# MCU.net
KiCad netlist of a schematic drawn in Altium Designer
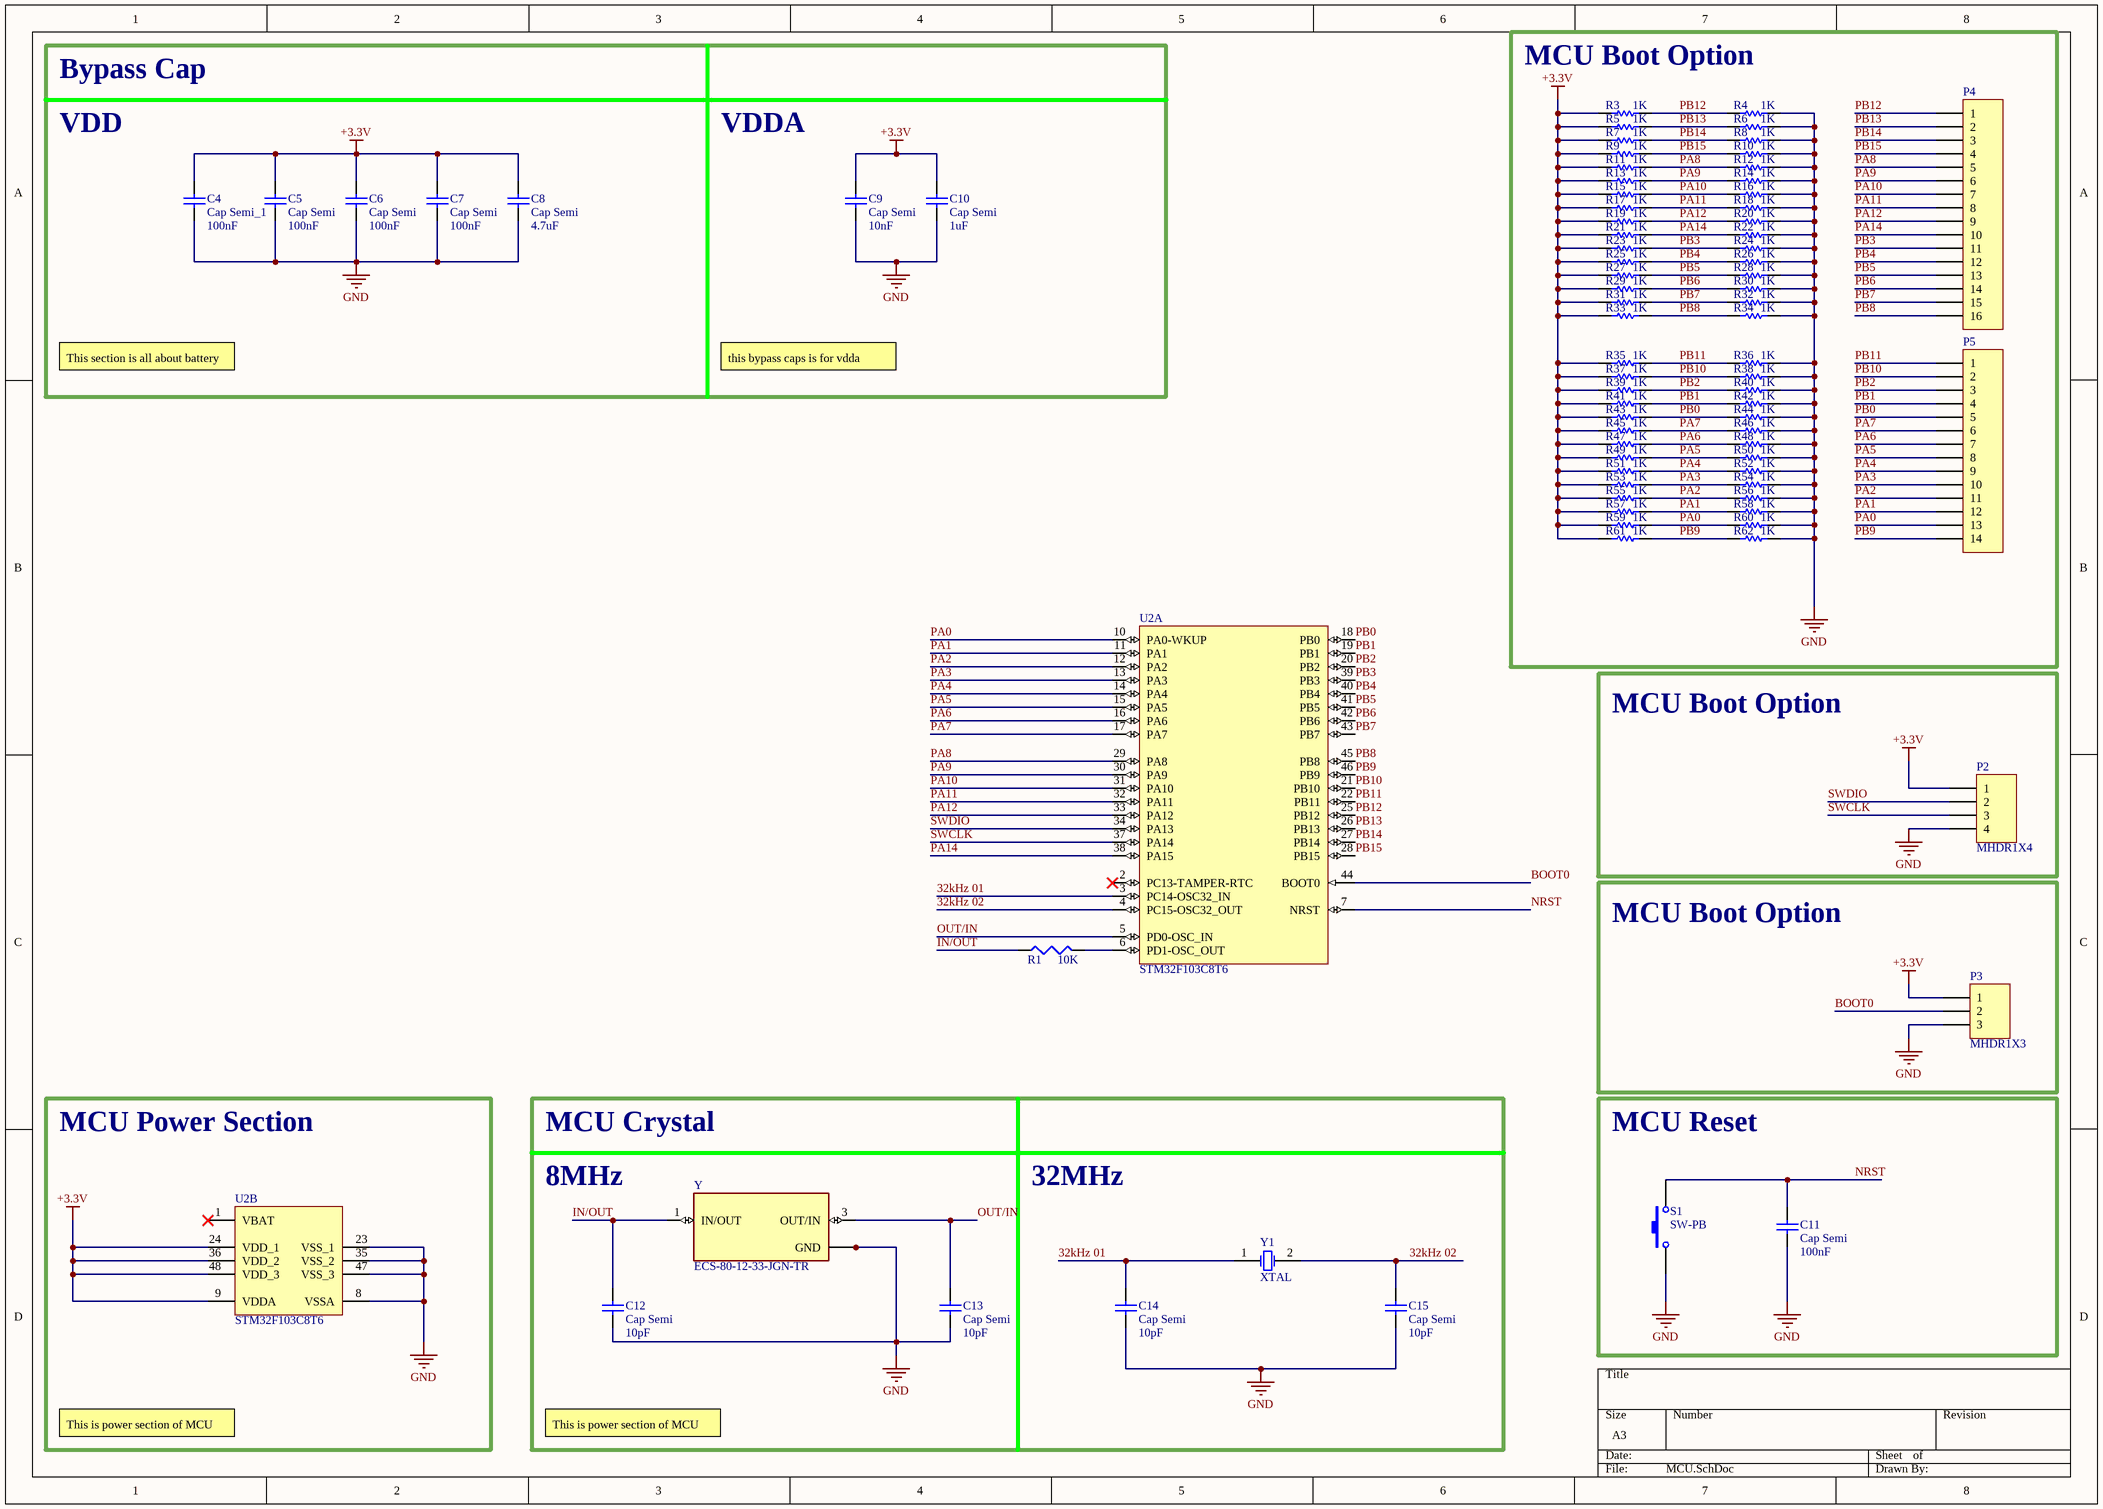
[diagram p0: MCU.SchDoc]

(export (version "E")
  (design (tool "Eeschema 10.0.6"))
  (components
    (comp (ref "C4")
      (value "Cap Semi_1")
      (footprint "1608[0603]")
      (description "Capacitor (Semiconductor SIM Model)")
      (fields (field (name "ALTIUM_VALUE") "100nF") (field (name "PUBLISHER") "Altium Limited"))
      (libsource (lib "Udemy Course") (part "Cap Semi_1"))
    )
    (comp (ref "C5")
      (value "Cap Semi")
      (footprint "1608[0603]")
      (description "Capacitor (Semiconductor SIM Model)")
      (fields (field (name "ALTIUM_VALUE") "100nF") (field (name "PUBLISHER") "Altium Limited"))
      (libsource (lib "Miscellaneous Devices") (part "Cap Semi"))
    )
    (comp (ref "C6")
      (value "Cap Semi")
      (footprint "1608[0603]")
      (description "Capacitor (Semiconductor SIM Model)")
      (fields (field (name "ALTIUM_VALUE") "100nF") (field (name "PUBLISHER") "Altium Limited"))
      (libsource (lib "Miscellaneous Devices") (part "Cap Semi"))
    )
    (comp (ref "C7")
      (value "Cap Semi")
      (footprint "1608[0603]")
      (description "Capacitor (Semiconductor SIM Model)")
      (fields (field (name "ALTIUM_VALUE") "100nF") (field (name "PUBLISHER") "Altium Limited"))
      (libsource (lib "Miscellaneous Devices") (part "Cap Semi"))
    )
    (comp (ref "C8")
      (value "Cap Semi")
      (footprint "1608[0603]")
      (description "Capacitor (Semiconductor SIM Model)")
      (fields (field (name "ALTIUM_VALUE") "4.7uF") (field (name "PUBLISHER") "Altium Limited"))
      (libsource (lib "Miscellaneous Devices") (part "Cap Semi"))
    )
    (comp (ref "C9")
      (value "Cap Semi")
      (footprint "1608[0603]")
      (description "Capacitor (Semiconductor SIM Model)")
      (fields (field (name "ALTIUM_VALUE") "10nF") (field (name "PUBLISHER") "Altium Limited"))
      (libsource (lib "Miscellaneous Devices") (part "Cap Semi"))
    )
    (comp (ref "C10")
      (value "Cap Semi")
      (footprint "1608[0603]")
      (description "Capacitor (Semiconductor SIM Model)")
      (fields (field (name "ALTIUM_VALUE") "1uF") (field (name "PUBLISHER") "Altium Limited"))
      (libsource (lib "Miscellaneous Devices") (part "Cap Semi"))
    )
    (comp (ref "C11")
      (value "Cap Semi")
      (footprint "1608[0603]")
      (description "Capacitor (Semiconductor SIM Model)")
      (fields (field (name "ALTIUM_VALUE") "100nF") (field (name "PUBLISHER") "Altium Limited"))
      (libsource (lib "Miscellaneous Devices") (part "Cap Semi"))
    )
    (comp (ref "C12")
      (value "Cap Semi")
      (footprint "0402")
      (description "Capacitor (Semiconductor SIM Model)")
      (fields (field (name "ALTIUM_VALUE") "10pF") (field (name "PUBLISHER") "Altium Limited"))
      (libsource (lib "Miscellaneous Devices") (part "Cap Semi"))
    )
    (comp (ref "C13")
      (value "Cap Semi")
      (footprint "0402")
      (description "Capacitor (Semiconductor SIM Model)")
      (fields (field (name "ALTIUM_VALUE") "10pF") (field (name "PUBLISHER") "Altium Limited"))
      (libsource (lib "Miscellaneous Devices") (part "Cap Semi"))
    )
    (comp (ref "C14")
      (value "Cap Semi")
      (footprint "0402")
      (description "Capacitor (Semiconductor SIM Model)")
      (fields (field (name "ALTIUM_VALUE") "10pF") (field (name "PUBLISHER") "Altium Limited"))
      (libsource (lib "Miscellaneous Devices") (part "Cap Semi"))
    )
    (comp (ref "C15")
      (value "Cap Semi")
      (footprint "0402")
      (description "Capacitor (Semiconductor SIM Model)")
      (fields (field (name "ALTIUM_VALUE") "10pF") (field (name "PUBLISHER") "Altium Limited"))
      (libsource (lib "Miscellaneous Devices") (part "Cap Semi"))
    )
    (comp (ref "P2")
      (value "MHDR1X4")
      (footprint "MHDR1X4body")
      (description "Header, 4-Pin")
      (fields (field (name "PUBLISHER") "Altium Limited"))
      (libsource (lib "Miscellaneous Connectors") (part "MHDR1X4"))
    )
    (comp (ref "P3")
      (value "MHDR1X3")
      (footprint "MHDR1X3body")
      (description "Header, 3-Pin")
      (fields (field (name "PUBLISHER") "Altium Limited"))
      (libsource (lib "Miscellaneous Connectors") (part "MHDR1X3"))
    )
    (comp (ref "P4")
      (value "Header 16")
      (footprint "MY_FE16")
      (description "Header, 16-Pin")
      (fields (field (name "ASID PART NUMBER") "Header 16-AS"))
      (libsource (lib "Udemy Library") (part "Header 16"))
    )
    (comp (ref "P5")
      (value "Header 14")
      (footprint "MY_FE14")
      (description "Header, 14-Pin")
      (fields (field (name "ASID PART NUMBER") "Header 14-AS"))
      (libsource (lib "Udemy Library") (part "Header 14"))
    )
    (comp (ref "R1")
      (value "10K")
      (footprint "J1-0603")
      (description "Resistor")
      (fields (field (name "Comment") "Res3") (field (name "PUBLISHER") "Altium Limited"))
      (libsource (lib "Miscellaneous Devices") (part "Res3"))
    )
    (comp (ref "R3")
      (value "1K")
      (footprint "MY_0603")
      (description "Standard resistor")
      (fields (field (name "ASID PART NUMBER") "Res-AS"))
      (libsource (lib "Udemy Library") (part "Res"))
    )
    (comp (ref "R4")
      (value "1K")
      (footprint "MY_0603")
      (description "Standard resistor")
      (fields (field (name "ASID PART NUMBER") "Res-AS"))
      (libsource (lib "Udemy Library") (part "Res"))
    )
    (comp (ref "R5")
      (value "1K")
      (footprint "MY_0603")
      (description "Standard resistor")
      (fields (field (name "ASID PART NUMBER") "Res-AS"))
      (libsource (lib "Udemy Library") (part "Res"))
    )
    (comp (ref "R6")
      (value "1K")
      (footprint "MY_0603")
      (description "Standard resistor")
      (fields (field (name "ASID PART NUMBER") "Res-AS"))
      (libsource (lib "Udemy Library") (part "Res"))
    )
    (comp (ref "R7")
      (value "1K")
      (footprint "MY_0603")
      (description "Standard resistor")
      (fields (field (name "ASID PART NUMBER") "Res-AS"))
      (libsource (lib "Udemy Library") (part "Res"))
    )
    (comp (ref "R8")
      (value "1K")
      (footprint "MY_0603")
      (description "Standard resistor")
      (fields (field (name "ASID PART NUMBER") "Res-AS"))
      (libsource (lib "Udemy Library") (part "Res"))
    )
    (comp (ref "R9")
      (value "1K")
      (footprint "MY_0603")
      (description "Standard resistor")
      (fields (field (name "ASID PART NUMBER") "Res-AS"))
      (libsource (lib "Udemy Library") (part "Res"))
    )
    (comp (ref "R10")
      (value "1K")
      (footprint "MY_0603")
      (description "Standard resistor")
      (fields (field (name "ASID PART NUMBER") "Res-AS"))
      (libsource (lib "Udemy Library") (part "Res"))
    )
    (comp (ref "R11")
      (value "1K")
      (footprint "MY_0603")
      (description "Standard resistor")
      (fields (field (name "ASID PART NUMBER") "Res-AS"))
      (libsource (lib "Udemy Library") (part "Res"))
    )
    (comp (ref "R12")
      (value "1K")
      (footprint "MY_0603")
      (description "Standard resistor")
      (fields (field (name "ASID PART NUMBER") "Res-AS"))
      (libsource (lib "Udemy Library") (part "Res"))
    )
    (comp (ref "R13")
      (value "1K")
      (footprint "MY_0603")
      (description "Standard resistor")
      (fields (field (name "ASID PART NUMBER") "Res-AS"))
      (libsource (lib "Udemy Library") (part "Res"))
    )
    (comp (ref "R14")
      (value "1K")
      (footprint "MY_0603")
      (description "Standard resistor")
      (fields (field (name "ASID PART NUMBER") "Res-AS"))
      (libsource (lib "Udemy Library") (part "Res"))
    )
    (comp (ref "R15")
      (value "1K")
      (footprint "MY_0603")
      (description "Standard resistor")
      (fields (field (name "ASID PART NUMBER") "Res-AS"))
      (libsource (lib "Udemy Library") (part "Res"))
    )
    (comp (ref "R16")
      (value "1K")
      (footprint "MY_0603")
      (description "Standard resistor")
      (fields (field (name "ASID PART NUMBER") "Res-AS"))
      (libsource (lib "Udemy Library") (part "Res"))
    )
    (comp (ref "R17")
      (value "1K")
      (footprint "MY_0603")
      (description "Standard resistor")
      (fields (field (name "ASID PART NUMBER") "Res-AS"))
      (libsource (lib "Udemy Library") (part "Res"))
    )
    (comp (ref "R18")
      (value "1K")
      (footprint "MY_0603")
      (description "Standard resistor")
      (fields (field (name "ASID PART NUMBER") "Res-AS"))
      (libsource (lib "Udemy Library") (part "Res"))
    )
    (comp (ref "R19")
      (value "1K")
      (footprint "MY_0603")
      (description "Standard resistor")
      (fields (field (name "ASID PART NUMBER") "Res-AS"))
      (libsource (lib "Udemy Library") (part "Res"))
    )
    (comp (ref "R20")
      (value "1K")
      (footprint "MY_0603")
      (description "Standard resistor")
      (fields (field (name "ASID PART NUMBER") "Res-AS"))
      (libsource (lib "Udemy Library") (part "Res"))
    )
    (comp (ref "R21")
      (value "1K")
      (footprint "MY_0603")
      (description "Standard resistor")
      (fields (field (name "ASID PART NUMBER") "Res-AS"))
      (libsource (lib "Udemy Library") (part "Res"))
    )
    (comp (ref "R22")
      (value "1K")
      (footprint "MY_0603")
      (description "Standard resistor")
      (fields (field (name "ASID PART NUMBER") "Res-AS"))
      (libsource (lib "Udemy Library") (part "Res"))
    )
    (comp (ref "R23")
      (value "1K")
      (footprint "MY_0603")
      (description "Standard resistor")
      (fields (field (name "ASID PART NUMBER") "Res-AS"))
      (libsource (lib "Udemy Library") (part "Res"))
    )
    (comp (ref "R24")
      (value "1K")
      (footprint "MY_0603")
      (description "Standard resistor")
      (fields (field (name "ASID PART NUMBER") "Res-AS"))
      (libsource (lib "Udemy Library") (part "Res"))
    )
    (comp (ref "R25")
      (value "1K")
      (footprint "MY_0603")
      (description "Standard resistor")
      (fields (field (name "ASID PART NUMBER") "Res-AS"))
      (libsource (lib "Udemy Library") (part "Res"))
    )
    (comp (ref "R26")
      (value "1K")
      (footprint "MY_0603")
      (description "Standard resistor")
      (fields (field (name "ASID PART NUMBER") "Res-AS"))
      (libsource (lib "Udemy Library") (part "Res"))
    )
    (comp (ref "R27")
      (value "1K")
      (footprint "MY_0603")
      (description "Standard resistor")
      (fields (field (name "ASID PART NUMBER") "Res-AS"))
      (libsource (lib "Udemy Library") (part "Res"))
    )
    (comp (ref "R28")
      (value "1K")
      (footprint "MY_0603")
      (description "Standard resistor")
      (fields (field (name "ASID PART NUMBER") "Res-AS"))
      (libsource (lib "Udemy Library") (part "Res"))
    )
    (comp (ref "R29")
      (value "1K")
      (footprint "MY_0603")
      (description "Standard resistor")
      (fields (field (name "ASID PART NUMBER") "Res-AS"))
      (libsource (lib "Udemy Library") (part "Res"))
    )
    (comp (ref "R30")
      (value "1K")
      (footprint "MY_0603")
      (description "Standard resistor")
      (fields (field (name "ASID PART NUMBER") "Res-AS"))
      (libsource (lib "Udemy Library") (part "Res"))
    )
    (comp (ref "R31")
      (value "1K")
      (footprint "MY_0603")
      (description "Standard resistor")
      (fields (field (name "ASID PART NUMBER") "Res-AS"))
      (libsource (lib "Udemy Library") (part "Res"))
    )
    (comp (ref "R32")
      (value "1K")
      (footprint "MY_0603")
      (description "Standard resistor")
      (fields (field (name "ASID PART NUMBER") "Res-AS"))
      (libsource (lib "Udemy Library") (part "Res"))
    )
    (comp (ref "R33")
      (value "1K")
      (footprint "MY_0603")
      (description "Standard resistor")
      (fields (field (name "ASID PART NUMBER") "Res-AS"))
      (libsource (lib "Udemy Library") (part "Res"))
    )
    (comp (ref "R34")
      (value "1K")
      (footprint "MY_0603")
      (description "Standard resistor")
      (fields (field (name "ASID PART NUMBER") "Res-AS"))
      (libsource (lib "Udemy Library") (part "Res"))
    )
    (comp (ref "R35")
      (value "1K")
      (footprint "MY_0603")
      (description "Standard resistor")
      (fields (field (name "ASID PART NUMBER") "Res-AS"))
      (libsource (lib "Udemy Library") (part "Res"))
    )
    (comp (ref "R36")
      (value "1K")
      (footprint "MY_0603")
      (description "Standard resistor")
      (fields (field (name "ASID PART NUMBER") "Res-AS"))
      (libsource (lib "Udemy Library") (part "Res"))
    )
    (comp (ref "R37")
      (value "1K")
      (footprint "MY_0603")
      (description "Standard resistor")
      (fields (field (name "ASID PART NUMBER") "Res-AS"))
      (libsource (lib "Udemy Library") (part "Res"))
    )
    (comp (ref "R38")
      (value "1K")
      (footprint "MY_0603")
      (description "Standard resistor")
      (fields (field (name "ASID PART NUMBER") "Res-AS"))
      (libsource (lib "Udemy Library") (part "Res"))
    )
    (comp (ref "R39")
      (value "1K")
      (footprint "MY_0603")
      (description "Standard resistor")
      (fields (field (name "ASID PART NUMBER") "Res-AS"))
      (libsource (lib "Udemy Library") (part "Res"))
    )
    (comp (ref "R40")
      (value "1K")
      (footprint "MY_0603")
      (description "Standard resistor")
      (fields (field (name "ASID PART NUMBER") "Res-AS"))
      (libsource (lib "Udemy Library") (part "Res"))
    )
    (comp (ref "R41")
      (value "1K")
      (footprint "MY_0603")
      (description "Standard resistor")
      (fields (field (name "ASID PART NUMBER") "Res-AS"))
      (libsource (lib "Udemy Library") (part "Res"))
    )
    (comp (ref "R42")
      (value "1K")
      (footprint "MY_0603")
      (description "Standard resistor")
      (fields (field (name "ASID PART NUMBER") "Res-AS"))
      (libsource (lib "Udemy Library") (part "Res"))
    )
    (comp (ref "R43")
      (value "1K")
      (footprint "MY_0603")
      (description "Standard resistor")
      (fields (field (name "ASID PART NUMBER") "Res-AS"))
      (libsource (lib "Udemy Library") (part "Res"))
    )
    (comp (ref "R44")
      (value "1K")
      (footprint "MY_0603")
      (description "Standard resistor")
      (fields (field (name "ASID PART NUMBER") "Res-AS"))
      (libsource (lib "Udemy Library") (part "Res"))
    )
    (comp (ref "R45")
      (value "1K")
      (footprint "MY_0603")
      (description "Standard resistor")
      (fields (field (name "ASID PART NUMBER") "Res-AS"))
      (libsource (lib "Udemy Library") (part "Res"))
    )
    (comp (ref "R46")
      (value "1K")
      (footprint "MY_0603")
      (description "Standard resistor")
      (fields (field (name "ASID PART NUMBER") "Res-AS"))
      (libsource (lib "Udemy Library") (part "Res"))
    )
    (comp (ref "R47")
      (value "1K")
      (footprint "MY_0603")
      (description "Standard resistor")
      (fields (field (name "ASID PART NUMBER") "Res-AS"))
      (libsource (lib "Udemy Library") (part "Res"))
    )
    (comp (ref "R48")
      (value "1K")
      (footprint "MY_0603")
      (description "Standard resistor")
      (fields (field (name "ASID PART NUMBER") "Res-AS"))
      (libsource (lib "Udemy Library") (part "Res"))
    )
    (comp (ref "R49")
      (value "1K")
      (footprint "MY_0603")
      (description "Standard resistor")
      (fields (field (name "ASID PART NUMBER") "Res-AS"))
      (libsource (lib "Udemy Library") (part "Res"))
    )
    (comp (ref "R50")
      (value "1K")
      (footprint "MY_0603")
      (description "Standard resistor")
      (fields (field (name "ASID PART NUMBER") "Res-AS"))
      (libsource (lib "Udemy Library") (part "Res"))
    )
    (comp (ref "R51")
      (value "1K")
      (footprint "MY_0603")
      (description "Standard resistor")
      (fields (field (name "ASID PART NUMBER") "Res-AS"))
      (libsource (lib "Udemy Library") (part "Res"))
    )
    (comp (ref "R52")
      (value "1K")
      (footprint "MY_0603")
      (description "Standard resistor")
      (fields (field (name "ASID PART NUMBER") "Res-AS"))
      (libsource (lib "Udemy Library") (part "Res"))
    )
    (comp (ref "R53")
      (value "1K")
      (footprint "MY_0603")
      (description "Standard resistor")
      (fields (field (name "ASID PART NUMBER") "Res-AS"))
      (libsource (lib "Udemy Library") (part "Res"))
    )
    (comp (ref "R54")
      (value "1K")
      (footprint "MY_0603")
      (description "Standard resistor")
      (fields (field (name "ASID PART NUMBER") "Res-AS"))
      (libsource (lib "Udemy Library") (part "Res"))
    )
    (comp (ref "R55")
      (value "1K")
      (footprint "MY_0603")
      (description "Standard resistor")
      (fields (field (name "ASID PART NUMBER") "Res-AS"))
      (libsource (lib "Udemy Library") (part "Res"))
    )
    (comp (ref "R56")
      (value "1K")
      (footprint "MY_0603")
      (description "Standard resistor")
      (fields (field (name "ASID PART NUMBER") "Res-AS"))
      (libsource (lib "Udemy Library") (part "Res"))
    )
    (comp (ref "R57")
      (value "1K")
      (footprint "MY_0603")
      (description "Standard resistor")
      (fields (field (name "ASID PART NUMBER") "Res-AS"))
      (libsource (lib "Udemy Library") (part "Res"))
    )
    (comp (ref "R58")
      (value "1K")
      (footprint "MY_0603")
      (description "Standard resistor")
      (fields (field (name "ASID PART NUMBER") "Res-AS"))
      (libsource (lib "Udemy Library") (part "Res"))
    )
    (comp (ref "R59")
      (value "1K")
      (footprint "MY_0603")
      (description "Standard resistor")
      (fields (field (name "ASID PART NUMBER") "Res-AS"))
      (libsource (lib "Udemy Library") (part "Res"))
    )
    (comp (ref "R60")
      (value "1K")
      (footprint "MY_0603")
      (description "Standard resistor")
      (fields (field (name "ASID PART NUMBER") "Res-AS"))
      (libsource (lib "Udemy Library") (part "Res"))
    )
    (comp (ref "R61")
      (value "1K")
      (footprint "MY_0603")
      (description "Standard resistor")
      (fields (field (name "ASID PART NUMBER") "Res-AS"))
      (libsource (lib "Udemy Library") (part "Res"))
    )
    (comp (ref "R62")
      (value "1K")
      (footprint "MY_0603")
      (description "Standard resistor")
      (fields (field (name "ASID PART NUMBER") "Res-AS"))
      (libsource (lib "Udemy Library") (part "Res"))
    )
    (comp (ref "S1")
      (value "SW-PB")
      (footprint "SPST-2_body")
      (description "Switch")
      (fields (field (name "PUBLISHER") "Altium Limited"))
      (libsource (lib "Miscellaneous Devices") (part "SW-PB"))
    )
    (comp (ref "U2")
      (value "STM32F103C8T6")
      (footprint "STM-LQFP48_N")
      (libsource (lib "PCB Udemy") (part "STM32F103C8T6"))
    )
    (comp (ref "Y")
      (value "ECS-80-12-33-JGN-TR")
      (footprint "8MHZCrystall")
      (description "8MHz Â±20ppm Crystal 12pF 400 Ohms 4-SMD, No Lead")
      (fields
        (field (name "MF") "ECS Inc.")
        (field (name "BUYPART") "https://www.snapeda.com/parts/ECS-80-12-33-JGN-TR/ECS%20Inc./view-part/4477300/?ref=eda")
      )
      (libsource (lib "ECS-80-12-33-JGN-TR") (part "ECS-80-12-33-JGN-TR"))
    )
    (comp (ref "Y1")
      (value "XTAL")
      (footprint "32768")
      (description "Crystal Oscillator")
      (fields (field (name "PUBLISHER") "Altium Limited"))
      (libsource (lib "Miscellaneous Devices") (part "XTAL"))
    )
  )
  (nets
    (net (code "1") (name "+3.3V") (class "Default")
      (node (ref "C10") (pin "2") (pinfunction "2_2") (pintype "passive"))
      (node (ref "C4") (pin "2") (pinfunction "2_2") (pintype "passive"))
      (node (ref "C5") (pin "2") (pinfunction "2_2") (pintype "passive"))
      (node (ref "C6") (pin "2") (pinfunction "2_2") (pintype "passive"))
      (node (ref "C7") (pin "2") (pinfunction "2_2") (pintype "passive"))
      (node (ref "C8") (pin "2") (pinfunction "2_2") (pintype "passive"))
      (node (ref "C9") (pin "2") (pinfunction "2_2") (pintype "passive"))
      (node (ref "P2") (pin "1") (pinfunction "1_1") (pintype "passive"))
      (node (ref "P3") (pin "1") (pinfunction "1_1") (pintype "passive"))
      (node (ref "R11") (pin "1") (pinfunction "1_1") (pintype "passive"))
      (node (ref "R13") (pin "1") (pinfunction "1_1") (pintype "passive"))
      (node (ref "R15") (pin "1") (pinfunction "1_1") (pintype "passive"))
      (node (ref "R17") (pin "1") (pinfunction "1_1") (pintype "passive"))
      (node (ref "R19") (pin "1") (pinfunction "1_1") (pintype "passive"))
      (node (ref "R21") (pin "1") (pinfunction "1_1") (pintype "passive"))
      (node (ref "R23") (pin "1") (pinfunction "1_1") (pintype "passive"))
      (node (ref "R25") (pin "1") (pinfunction "1_1") (pintype "passive"))
      (node (ref "R27") (pin "1") (pinfunction "1_1") (pintype "passive"))
      (node (ref "R29") (pin "1") (pinfunction "1_1") (pintype "passive"))
      (node (ref "R3") (pin "1") (pinfunction "1_1") (pintype "passive"))
      (node (ref "R31") (pin "1") (pinfunction "1_1") (pintype "passive"))
      (node (ref "R33") (pin "1") (pinfunction "1_1") (pintype "passive"))
      (node (ref "R35") (pin "1") (pinfunction "1_1") (pintype "passive"))
      (node (ref "R37") (pin "1") (pinfunction "1_1") (pintype "passive"))
      (node (ref "R39") (pin "1") (pinfunction "1_1") (pintype "passive"))
      (node (ref "R41") (pin "1") (pinfunction "1_1") (pintype "passive"))
      (node (ref "R43") (pin "1") (pinfunction "1_1") (pintype "passive"))
      (node (ref "R45") (pin "1") (pinfunction "1_1") (pintype "passive"))
      (node (ref "R47") (pin "1") (pinfunction "1_1") (pintype "passive"))
      (node (ref "R49") (pin "1") (pinfunction "1_1") (pintype "passive"))
      (node (ref "R5") (pin "1") (pinfunction "1_1") (pintype "passive"))
      (node (ref "R51") (pin "1") (pinfunction "1_1") (pintype "passive"))
      (node (ref "R53") (pin "1") (pinfunction "1_1") (pintype "passive"))
      (node (ref "R55") (pin "1") (pinfunction "1_1") (pintype "passive"))
      (node (ref "R57") (pin "1") (pinfunction "1_1") (pintype "passive"))
      (node (ref "R59") (pin "1") (pinfunction "1_1") (pintype "passive"))
      (node (ref "R61") (pin "1") (pinfunction "1_1") (pintype "passive"))
      (node (ref "R7") (pin "1") (pinfunction "1_1") (pintype "passive"))
      (node (ref "R9") (pin "1") (pinfunction "1_1") (pintype "passive"))
      (node (ref "U2") (pin "24") (pinfunction "VDD_1_24") (pintype "power_in"))
      (node (ref "U2") (pin "36") (pinfunction "VDD_2_36") (pintype "power_in"))
      (node (ref "U2") (pin "48") (pinfunction "VDD_3_48") (pintype "power_in"))
      (node (ref "U2") (pin "9") (pinfunction "VDDA_9") (pintype "power_in"))
    )
    (net (code "2") (name "/32kHz 01") (class "Default")
      (node (ref "C14") (pin "2") (pinfunction "2_2") (pintype "passive"))
      (node (ref "U2") (pin "3") (pinfunction "PC14-OSC32_IN_3") (pintype "bidirectional"))
      (node (ref "Y1") (pin "1") (pinfunction "OSC1_1") (pintype "passive"))
    )
    (net (code "3") (name "/32kHz 02") (class "Default")
      (node (ref "C15") (pin "2") (pinfunction "2_2") (pintype "passive"))
      (node (ref "U2") (pin "4") (pinfunction "PC15-OSC32_OUT_4") (pintype "bidirectional"))
      (node (ref "Y1") (pin "2") (pinfunction "OSC2_2") (pintype "passive"))
    )
    (net (code "4") (name "/BOOT0") (class "Default")
      (node (ref "P3") (pin "2") (pinfunction "2_2") (pintype "passive"))
      (node (ref "U2") (pin "44") (pinfunction "BOOT0_44") (pintype "input"))
    )
    (net (code "5") (name "/IN{slash}OUT") (class "Default")
      (node (ref "C12") (pin "1") (pinfunction "1_1") (pintype "passive"))
      (node (ref "R1") (pin "1") (pinfunction "1_1") (pintype "passive"))
      (node (ref "Y") (pin "1") (pinfunction "IN/OUT_1") (pintype "bidirectional"))
    )
    (net (code "6") (name "/NRST") (class "Default")
      (node (ref "C11") (pin "2") (pinfunction "2_2") (pintype "passive"))
      (node (ref "S1") (pin "2") (pinfunction "2_2") (pintype "passive"))
      (node (ref "U2") (pin "7") (pinfunction "NRST_7") (pintype "bidirectional"))
    )
    (net (code "7") (name "/OUT{slash}IN") (class "Default")
      (node (ref "C13") (pin "2") (pinfunction "2_2") (pintype "passive"))
      (node (ref "U2") (pin "5") (pinfunction "PD0-OSC_IN_5") (pintype "bidirectional"))
      (node (ref "Y") (pin "3") (pinfunction "OUT/IN_3") (pintype "bidirectional"))
    )
    (net (code "8") (name "/PA0") (class "Default")
      (node (ref "P5") (pin "13") (pinfunction "13_13") (pintype "passive"))
      (node (ref "R59") (pin "2") (pinfunction "2_2") (pintype "passive"))
      (node (ref "R60") (pin "1") (pinfunction "1_1") (pintype "passive"))
      (node (ref "U2") (pin "10") (pinfunction "PA0-WKUP_10") (pintype "bidirectional"))
    )
    (net (code "9") (name "/PA1") (class "Default")
      (node (ref "P5") (pin "12") (pinfunction "12_12") (pintype "passive"))
      (node (ref "R57") (pin "2") (pinfunction "2_2") (pintype "passive"))
      (node (ref "R58") (pin "1") (pinfunction "1_1") (pintype "passive"))
      (node (ref "U2") (pin "11") (pinfunction "PA1_11") (pintype "bidirectional"))
    )
    (net (code "10") (name "/PA2") (class "Default")
      (node (ref "P5") (pin "11") (pinfunction "11_11") (pintype "passive"))
      (node (ref "R55") (pin "2") (pinfunction "2_2") (pintype "passive"))
      (node (ref "R56") (pin "1") (pinfunction "1_1") (pintype "passive"))
      (node (ref "U2") (pin "12") (pinfunction "PA2_12") (pintype "bidirectional"))
    )
    (net (code "11") (name "/PA3") (class "Default")
      (node (ref "P5") (pin "10") (pinfunction "10_10") (pintype "passive"))
      (node (ref "R53") (pin "2") (pinfunction "2_2") (pintype "passive"))
      (node (ref "R54") (pin "1") (pinfunction "1_1") (pintype "passive"))
      (node (ref "U2") (pin "13") (pinfunction "PA3_13") (pintype "bidirectional"))
    )
    (net (code "12") (name "/PA4") (class "Default")
      (node (ref "P5") (pin "9") (pinfunction "9_9") (pintype "passive"))
      (node (ref "R51") (pin "2") (pinfunction "2_2") (pintype "passive"))
      (node (ref "R52") (pin "1") (pinfunction "1_1") (pintype "passive"))
      (node (ref "U2") (pin "14") (pinfunction "PA4_14") (pintype "bidirectional"))
    )
    (net (code "13") (name "/PA5") (class "Default")
      (node (ref "P5") (pin "8") (pinfunction "8_8") (pintype "passive"))
      (node (ref "R49") (pin "2") (pinfunction "2_2") (pintype "passive"))
      (node (ref "R50") (pin "1") (pinfunction "1_1") (pintype "passive"))
      (node (ref "U2") (pin "15") (pinfunction "PA5_15") (pintype "bidirectional"))
    )
    (net (code "14") (name "/PA6") (class "Default")
      (node (ref "P5") (pin "7") (pinfunction "7_7") (pintype "passive"))
      (node (ref "R47") (pin "2") (pinfunction "2_2") (pintype "passive"))
      (node (ref "R48") (pin "1") (pinfunction "1_1") (pintype "passive"))
      (node (ref "U2") (pin "16") (pinfunction "PA6_16") (pintype "bidirectional"))
    )
    (net (code "15") (name "/PA7") (class "Default")
      (node (ref "P5") (pin "6") (pinfunction "6_6") (pintype "passive"))
      (node (ref "R45") (pin "2") (pinfunction "2_2") (pintype "passive"))
      (node (ref "R46") (pin "1") (pinfunction "1_1") (pintype "passive"))
      (node (ref "U2") (pin "17") (pinfunction "PA7_17") (pintype "bidirectional"))
    )
    (net (code "16") (name "/PA8") (class "Default")
      (node (ref "P4") (pin "5") (pinfunction "5_5") (pintype "passive"))
      (node (ref "R11") (pin "2") (pinfunction "2_2") (pintype "passive"))
      (node (ref "R12") (pin "1") (pinfunction "1_1") (pintype "passive"))
      (node (ref "U2") (pin "29") (pinfunction "PA8_29") (pintype "bidirectional"))
    )
    (net (code "17") (name "/PA9") (class "Default")
      (node (ref "P4") (pin "6") (pinfunction "6_6") (pintype "passive"))
      (node (ref "R13") (pin "2") (pinfunction "2_2") (pintype "passive"))
      (node (ref "R14") (pin "1") (pinfunction "1_1") (pintype "passive"))
      (node (ref "U2") (pin "30") (pinfunction "PA9_30") (pintype "bidirectional"))
    )
    (net (code "18") (name "/PA10") (class "Default")
      (node (ref "P4") (pin "7") (pinfunction "7_7") (pintype "passive"))
      (node (ref "R15") (pin "2") (pinfunction "2_2") (pintype "passive"))
      (node (ref "R16") (pin "1") (pinfunction "1_1") (pintype "passive"))
      (node (ref "U2") (pin "31") (pinfunction "PA10_31") (pintype "bidirectional"))
    )
    (net (code "19") (name "/PA11") (class "Default")
      (node (ref "P4") (pin "8") (pinfunction "8_8") (pintype "passive"))
      (node (ref "R17") (pin "2") (pinfunction "2_2") (pintype "passive"))
      (node (ref "R18") (pin "1") (pinfunction "1_1") (pintype "passive"))
      (node (ref "U2") (pin "32") (pinfunction "PA11_32") (pintype "bidirectional"))
    )
    (net (code "20") (name "/PA12") (class "Default")
      (node (ref "P4") (pin "9") (pinfunction "9_9") (pintype "passive"))
      (node (ref "R19") (pin "2") (pinfunction "2_2") (pintype "passive"))
      (node (ref "R20") (pin "1") (pinfunction "1_1") (pintype "passive"))
      (node (ref "U2") (pin "33") (pinfunction "PA12_33") (pintype "bidirectional"))
    )
    (net (code "21") (name "/PA14") (class "Default")
      (node (ref "P4") (pin "10") (pinfunction "10_10") (pintype "passive"))
      (node (ref "R21") (pin "2") (pinfunction "2_2") (pintype "passive"))
      (node (ref "R22") (pin "1") (pinfunction "1_1") (pintype "passive"))
      (node (ref "U2") (pin "38") (pinfunction "PA15_38") (pintype "bidirectional"))
    )
    (net (code "22") (name "/PB0") (class "Default")
      (node (ref "P5") (pin "5") (pinfunction "5_5") (pintype "passive"))
      (node (ref "R43") (pin "2") (pinfunction "2_2") (pintype "passive"))
      (node (ref "R44") (pin "1") (pinfunction "1_1") (pintype "passive"))
      (node (ref "U2") (pin "18") (pinfunction "PB0_18") (pintype "bidirectional"))
    )
    (net (code "23") (name "/PB1") (class "Default")
      (node (ref "P5") (pin "4") (pinfunction "4_4") (pintype "passive"))
      (node (ref "R41") (pin "2") (pinfunction "2_2") (pintype "passive"))
      (node (ref "R42") (pin "1") (pinfunction "1_1") (pintype "passive"))
      (node (ref "U2") (pin "19") (pinfunction "PB1_19") (pintype "bidirectional"))
    )
    (net (code "24") (name "/PB2") (class "Default")
      (node (ref "P5") (pin "3") (pinfunction "3_3") (pintype "passive"))
      (node (ref "R39") (pin "2") (pinfunction "2_2") (pintype "passive"))
      (node (ref "R40") (pin "1") (pinfunction "1_1") (pintype "passive"))
      (node (ref "U2") (pin "20") (pinfunction "PB2_20") (pintype "bidirectional"))
    )
    (net (code "25") (name "/PB3") (class "Default")
      (node (ref "P4") (pin "11") (pinfunction "11_11") (pintype "passive"))
      (node (ref "R23") (pin "2") (pinfunction "2_2") (pintype "passive"))
      (node (ref "R24") (pin "1") (pinfunction "1_1") (pintype "passive"))
      (node (ref "U2") (pin "39") (pinfunction "PB3_39") (pintype "bidirectional"))
    )
    (net (code "26") (name "/PB4") (class "Default")
      (node (ref "P4") (pin "12") (pinfunction "12_12") (pintype "passive"))
      (node (ref "R25") (pin "2") (pinfunction "2_2") (pintype "passive"))
      (node (ref "R26") (pin "1") (pinfunction "1_1") (pintype "passive"))
      (node (ref "U2") (pin "40") (pinfunction "PB4_40") (pintype "bidirectional"))
    )
    (net (code "27") (name "/PB5") (class "Default")
      (node (ref "P4") (pin "13") (pinfunction "13_13") (pintype "passive"))
      (node (ref "R27") (pin "2") (pinfunction "2_2") (pintype "passive"))
      (node (ref "R28") (pin "1") (pinfunction "1_1") (pintype "passive"))
      (node (ref "U2") (pin "41") (pinfunction "PB5_41") (pintype "bidirectional"))
    )
    (net (code "28") (name "/PB6") (class "Default")
      (node (ref "P4") (pin "14") (pinfunction "14_14") (pintype "passive"))
      (node (ref "R29") (pin "2") (pinfunction "2_2") (pintype "passive"))
      (node (ref "R30") (pin "1") (pinfunction "1_1") (pintype "passive"))
      (node (ref "U2") (pin "42") (pinfunction "PB6_42") (pintype "bidirectional"))
    )
    (net (code "29") (name "/PB7") (class "Default")
      (node (ref "P4") (pin "15") (pinfunction "15_15") (pintype "passive"))
      (node (ref "R31") (pin "2") (pinfunction "2_2") (pintype "passive"))
      (node (ref "R32") (pin "1") (pinfunction "1_1") (pintype "passive"))
      (node (ref "U2") (pin "43") (pinfunction "PB7_43") (pintype "bidirectional"))
    )
    (net (code "30") (name "/PB8") (class "Default")
      (node (ref "P4") (pin "16") (pinfunction "16_16") (pintype "passive"))
      (node (ref "R33") (pin "2") (pinfunction "2_2") (pintype "passive"))
      (node (ref "R34") (pin "1") (pinfunction "1_1") (pintype "passive"))
      (node (ref "U2") (pin "45") (pinfunction "PB8_45") (pintype "bidirectional"))
    )
    (net (code "31") (name "/PB9") (class "Default")
      (node (ref "P5") (pin "14") (pinfunction "14_14") (pintype "passive"))
      (node (ref "R61") (pin "2") (pinfunction "2_2") (pintype "passive"))
      (node (ref "R62") (pin "1") (pinfunction "1_1") (pintype "passive"))
      (node (ref "U2") (pin "46") (pinfunction "PB9_46") (pintype "bidirectional"))
    )
    (net (code "32") (name "/PB10") (class "Default")
      (node (ref "P5") (pin "2") (pinfunction "2_2") (pintype "passive"))
      (node (ref "R37") (pin "2") (pinfunction "2_2") (pintype "passive"))
      (node (ref "R38") (pin "1") (pinfunction "1_1") (pintype "passive"))
      (node (ref "U2") (pin "21") (pinfunction "PB10_21") (pintype "bidirectional"))
    )
    (net (code "33") (name "/PB11") (class "Default")
      (node (ref "P5") (pin "1") (pinfunction "1_1") (pintype "passive"))
      (node (ref "R35") (pin "2") (pinfunction "2_2") (pintype "passive"))
      (node (ref "R36") (pin "1") (pinfunction "1_1") (pintype "passive"))
      (node (ref "U2") (pin "22") (pinfunction "PB11_22") (pintype "bidirectional"))
    )
    (net (code "34") (name "/PB12") (class "Default")
      (node (ref "P4") (pin "1") (pinfunction "1_1") (pintype "passive"))
      (node (ref "R3") (pin "2") (pinfunction "2_2") (pintype "passive"))
      (node (ref "R4") (pin "1") (pinfunction "1_1") (pintype "passive"))
      (node (ref "U2") (pin "25") (pinfunction "PB12_25") (pintype "bidirectional"))
    )
    (net (code "35") (name "/PB13") (class "Default")
      (node (ref "P4") (pin "2") (pinfunction "2_2") (pintype "passive"))
      (node (ref "R5") (pin "2") (pinfunction "2_2") (pintype "passive"))
      (node (ref "R6") (pin "1") (pinfunction "1_1") (pintype "passive"))
      (node (ref "U2") (pin "26") (pinfunction "PB13_26") (pintype "bidirectional"))
    )
    (net (code "36") (name "/PB14") (class "Default")
      (node (ref "P4") (pin "3") (pinfunction "3_3") (pintype "passive"))
      (node (ref "R7") (pin "2") (pinfunction "2_2") (pintype "passive"))
      (node (ref "R8") (pin "1") (pinfunction "1_1") (pintype "passive"))
      (node (ref "U2") (pin "27") (pinfunction "PB14_27") (pintype "bidirectional"))
    )
    (net (code "37") (name "/PB15") (class "Default")
      (node (ref "P4") (pin "4") (pinfunction "4_4") (pintype "passive"))
      (node (ref "R10") (pin "1") (pinfunction "1_1") (pintype "passive"))
      (node (ref "R9") (pin "2") (pinfunction "2_2") (pintype "passive"))
      (node (ref "U2") (pin "28") (pinfunction "PB15_28") (pintype "bidirectional"))
    )
    (net (code "38") (name "/SWCLK") (class "Default")
      (node (ref "P2") (pin "3") (pinfunction "3_3") (pintype "passive"))
      (node (ref "U2") (pin "37") (pinfunction "PA14_37") (pintype "bidirectional"))
    )
    (net (code "39") (name "/SWDIO") (class "Default")
      (node (ref "P2") (pin "2") (pinfunction "2_2") (pintype "passive"))
      (node (ref "U2") (pin "34") (pinfunction "PA13_34") (pintype "bidirectional"))
    )
    (net (code "40") (name "GND") (class "Default")
      (node (ref "C10") (pin "1") (pinfunction "1_1") (pintype "passive"))
      (node (ref "C11") (pin "1") (pinfunction "1_1") (pintype "passive"))
      (node (ref "C12") (pin "2") (pinfunction "2_2") (pintype "passive"))
      (node (ref "C13") (pin "1") (pinfunction "1_1") (pintype "passive"))
      (node (ref "C14") (pin "1") (pinfunction "1_1") (pintype "passive"))
      (node (ref "C15") (pin "1") (pinfunction "1_1") (pintype "passive"))
      (node (ref "C4") (pin "1") (pinfunction "1_1") (pintype "passive"))
      (node (ref "C5") (pin "1") (pinfunction "1_1") (pintype "passive"))
      (node (ref "C6") (pin "1") (pinfunction "1_1") (pintype "passive"))
      (node (ref "C7") (pin "1") (pinfunction "1_1") (pintype "passive"))
      (node (ref "C8") (pin "1") (pinfunction "1_1") (pintype "passive"))
      (node (ref "C9") (pin "1") (pinfunction "1_1") (pintype "passive"))
      (node (ref "P2") (pin "4") (pinfunction "4_4") (pintype "passive"))
      (node (ref "P3") (pin "3") (pinfunction "3_3") (pintype "passive"))
      (node (ref "R10") (pin "2") (pinfunction "2_2") (pintype "passive"))
      (node (ref "R12") (pin "2") (pinfunction "2_2") (pintype "passive"))
      (node (ref "R14") (pin "2") (pinfunction "2_2") (pintype "passive"))
      (node (ref "R16") (pin "2") (pinfunction "2_2") (pintype "passive"))
      (node (ref "R18") (pin "2") (pinfunction "2_2") (pintype "passive"))
      (node (ref "R20") (pin "2") (pinfunction "2_2") (pintype "passive"))
      (node (ref "R22") (pin "2") (pinfunction "2_2") (pintype "passive"))
      (node (ref "R24") (pin "2") (pinfunction "2_2") (pintype "passive"))
      (node (ref "R26") (pin "2") (pinfunction "2_2") (pintype "passive"))
      (node (ref "R28") (pin "2") (pinfunction "2_2") (pintype "passive"))
      (node (ref "R30") (pin "2") (pinfunction "2_2") (pintype "passive"))
      (node (ref "R32") (pin "2") (pinfunction "2_2") (pintype "passive"))
      (node (ref "R34") (pin "2") (pinfunction "2_2") (pintype "passive"))
      (node (ref "R36") (pin "2") (pinfunction "2_2") (pintype "passive"))
      (node (ref "R38") (pin "2") (pinfunction "2_2") (pintype "passive"))
      (node (ref "R4") (pin "2") (pinfunction "2_2") (pintype "passive"))
      (node (ref "R40") (pin "2") (pinfunction "2_2") (pintype "passive"))
      (node (ref "R42") (pin "2") (pinfunction "2_2") (pintype "passive"))
      (node (ref "R44") (pin "2") (pinfunction "2_2") (pintype "passive"))
      (node (ref "R46") (pin "2") (pinfunction "2_2") (pintype "passive"))
      (node (ref "R48") (pin "2") (pinfunction "2_2") (pintype "passive"))
      (node (ref "R50") (pin "2") (pinfunction "2_2") (pintype "passive"))
      (node (ref "R52") (pin "2") (pinfunction "2_2") (pintype "passive"))
      (node (ref "R54") (pin "2") (pinfunction "2_2") (pintype "passive"))
      (node (ref "R56") (pin "2") (pinfunction "2_2") (pintype "passive"))
      (node (ref "R58") (pin "2") (pinfunction "2_2") (pintype "passive"))
      (node (ref "R6") (pin "2") (pinfunction "2_2") (pintype "passive"))
      (node (ref "R60") (pin "2") (pinfunction "2_2") (pintype "passive"))
      (node (ref "R62") (pin "2") (pinfunction "2_2") (pintype "passive"))
      (node (ref "R8") (pin "2") (pinfunction "2_2") (pintype "passive"))
      (node (ref "S1") (pin "1") (pinfunction "1_1") (pintype "passive"))
      (node (ref "U2") (pin "23") (pinfunction "VSS_1_23") (pintype "power_in"))
      (node (ref "U2") (pin "35") (pinfunction "VSS_2_35") (pintype "power_in"))
      (node (ref "U2") (pin "47") (pinfunction "VSS_3_47") (pintype "power_in"))
      (node (ref "U2") (pin "8") (pinfunction "VSSA_8") (pintype "power_in"))
      (node (ref "Y") (pin "2") (pinfunction "GND_2") (pintype "power_in"))
      (node (ref "Y") (pin "4") (pinfunction "GND_4") (pintype "power_in"))
    )
    (net (code "41") (name "Net-(U2A-PD1-OSC_OUT)") (class "Default")
      (node (ref "R1") (pin "2") (pinfunction "2_2") (pintype "passive"))
      (node (ref "U2") (pin "6") (pinfunction "PD1-OSC_OUT_6") (pintype "bidirectional"))
    )
    (net (code "42") (name "unconnected-(U2A-PC13-TAMPER-RTC-Pad2)") (class "Default")
      (node (ref "U2") (pin "2") (pinfunction "PC13-TAMPER-RTC_2") (pintype "bidirectional+no_connect"))
    )
    (net (code "43") (name "unconnected-(U2B-VBAT-Pad1)") (class "Default")
      (node (ref "U2") (pin "1") (pinfunction "VBAT_1") (pintype "power_in+no_connect"))
    )
  )
)
